# PCB-IO-PROTECTION-INDUCTANCE-2.net
KiCad netlist of a schematic drawn in Altium Designer
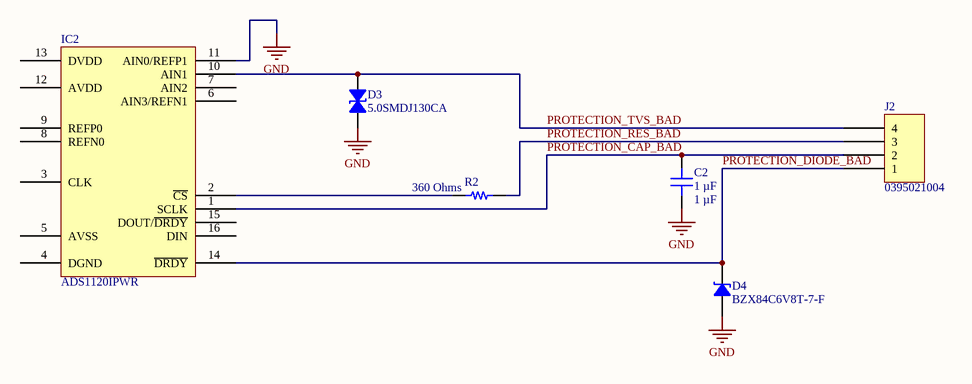
[diagram p0: PCB-IO-PROTECTION-INDUCTANCE-2.SchDoc]

(export (version "E")
  (design (tool "Eeschema 10.0.6"))
  (components
    (comp (ref "C2")
      (value "1 µF")
      (footprint "CAP 0603_1608")
      (description "CAP CER 1UF 16V X7R 0603")
      (fields (field (name "PART NUMBER") "C0603C105K4RACAUTO") (field (name "ALTIUM_VALUE") "1 µF"))
      (libsource (lib "Celestial Altium Library - altium_library") (part "Capacitor"))
    )
    (comp (ref "D3")
      (value "5.0SMDJ130CA")
      (footprint "DO214AB SMC")
      (description "TVS DIODE 130VWM 209VC DO214AB")
      (libsource (lib "Celestial Altium Library - altium_library") (part "Diode TVS"))
    )
    (comp (ref "D4")
      (value "BZX84C6V8T-7-F")
      (footprint "DIODES SOT-523")
      (description "DIODE ZENER 6.8V 150MW SOT523")
      (libsource (lib "Celestial Altium Library - altium_library") (part "Diode Zener"))
    )
    (comp (ref "IC2")
      (value "ADS1120IPWR")
      (footprint "TI TSSOP-16 PW")
      (description "IC ADC 16BIT SIGMA-DELTA 16TSSOP")
      (libsource (lib "Celestial Altium Library - altium_library") (part "TI ADS1120 TSSOP"))
    )
    (comp (ref "J2")
      (value "0395021004")
      (footprint "MOLEX 395021004")
      (description "TERM BLOCK HDR 4POS 90DEG 3.5MM")
      (fields (field (name "MANUFACTURER") "Molex"))
      (libsource (lib "Celestial Altium Library - altium_library") (part "4 Pin"))
    )
    (comp (ref "R2")
      (value "360 Ohms")
      (footprint "RES 0603_1608")
      (description "RES SMD 360 OHM 0.1% 1/5W 0603")
      (fields (field (name "PART NUMBER") "ERJ-PB3B3600V"))
      (libsource (lib "Celestial Altium Library - altium_library") (part "Resistor"))
    )
  )
  (nets
    (net (code "1") (name "/PROTECTION_CAP_BAD") (class "Default")
      (node (ref "C2") (pin "2") (pinfunction "2_2") (pintype "passive"))
      (node (ref "IC2") (pin "1") (pinfunction "SCLK_1") (pintype "passive"))
      (node (ref "J2") (pin "2") (pinfunction "2_2") (pintype "passive"))
    )
    (net (code "2") (name "/PROTECTION_DIODE_BAD") (class "Default")
      (node (ref "D4") (pin "2") (pinfunction "2_2") (pintype "passive"))
      (node (ref "IC2") (pin "14") (pinfunction "~{DRDY}_14") (pintype "passive"))
      (node (ref "J2") (pin "1") (pinfunction "1_1") (pintype "passive"))
    )
    (net (code "3") (name "/PROTECTION_RES_BAD") (class "Default")
      (node (ref "J2") (pin "3") (pinfunction "3_3") (pintype "passive"))
      (node (ref "R2") (pin "2") (pinfunction "2_2") (pintype "passive"))
    )
    (net (code "4") (name "/PROTECTION_TVS_BAD") (class "Default")
      (node (ref "D3") (pin "2") (pinfunction "2_2") (pintype "passive"))
      (node (ref "IC2") (pin "10") (pinfunction "AIN1_10") (pintype "passive"))
      (node (ref "J2") (pin "4") (pinfunction "4_4") (pintype "passive"))
    )
    (net (code "5") (name "GND") (class "Default")
      (node (ref "C2") (pin "1") (pinfunction "1_1") (pintype "passive"))
      (node (ref "D3") (pin "1") (pinfunction "1_1") (pintype "passive"))
      (node (ref "D4") (pin "1") (pinfunction "1_1") (pintype "passive"))
      (node (ref "IC2") (pin "11") (pinfunction "AIN0/REFP1_11") (pintype "passive"))
    )
    (net (code "6") (name "Net-(IC2-~{CS})") (class "Default")
      (node (ref "IC2") (pin "2") (pinfunction "~{CS}_2") (pintype "passive"))
      (node (ref "R2") (pin "1") (pinfunction "1_1") (pintype "passive"))
    )
    (net (code "7") (name "unconnected-(IC2-AIN2-Pad7)") (class "Default")
      (node (ref "IC2") (pin "7") (pinfunction "AIN2_7") (pintype "passive"))
    )
    (net (code "8") (name "unconnected-(IC2-AIN3{slash}REFN1-Pad6)") (class "Default")
      (node (ref "IC2") (pin "6") (pinfunction "AIN3/REFN1_6") (pintype "passive"))
    )
    (net (code "9") (name "unconnected-(IC2-AVDD-Pad12)") (class "Default")
      (node (ref "IC2") (pin "12") (pinfunction "AVDD_12") (pintype "passive"))
    )
    (net (code "10") (name "unconnected-(IC2-AVSS-Pad5)") (class "Default")
      (node (ref "IC2") (pin "5") (pinfunction "AVSS_5") (pintype "passive"))
    )
    (net (code "11") (name "unconnected-(IC2-CLK-Pad3)") (class "Default")
      (node (ref "IC2") (pin "3") (pinfunction "CLK_3") (pintype "passive"))
    )
    (net (code "12") (name "unconnected-(IC2-DGND-Pad4)") (class "Default")
      (node (ref "IC2") (pin "4") (pinfunction "DGND_4") (pintype "passive"))
    )
    (net (code "13") (name "unconnected-(IC2-DIN-Pad16)") (class "Default")
      (node (ref "IC2") (pin "16") (pinfunction "DIN_16") (pintype "passive"))
    )
    (net (code "14") (name "unconnected-(IC2-DOUT{slash}~{DRDY}-Pad15)") (class "Default")
      (node (ref "IC2") (pin "15") (pinfunction "DOUT/~{DRDY}_15") (pintype "passive"))
    )
    (net (code "15") (name "unconnected-(IC2-DVDD-Pad13)") (class "Default")
      (node (ref "IC2") (pin "13") (pinfunction "DVDD_13") (pintype "passive"))
    )
    (net (code "16") (name "unconnected-(IC2-REFN0-Pad8)") (class "Default")
      (node (ref "IC2") (pin "8") (pinfunction "REFN0_8") (pintype "passive"))
    )
    (net (code "17") (name "unconnected-(IC2-REFP0-Pad9)") (class "Default")
      (node (ref "IC2") (pin "9") (pinfunction "REFP0_9") (pintype "passive"))
    )
  )
)
